# untitled.net
KiCad netlist of a schematic drawn in EAGLE
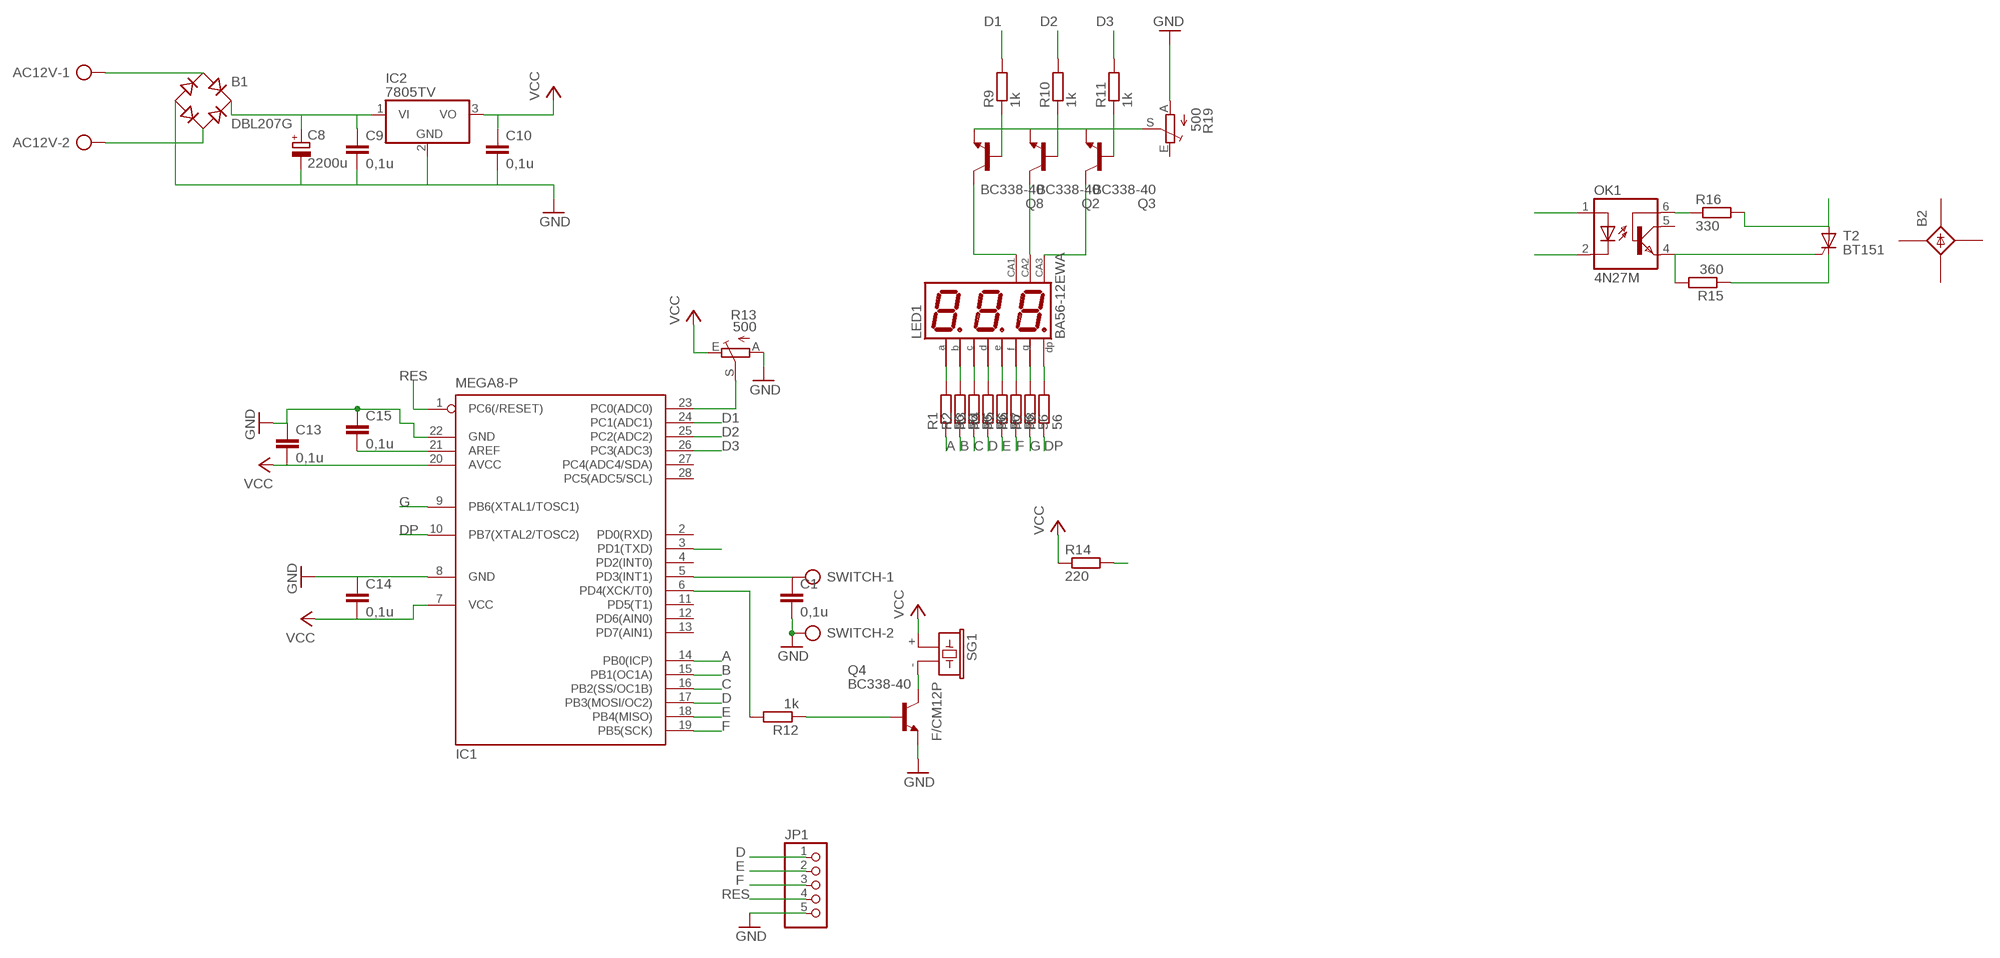
[diagram p0: schematic, sheet 1]

(export (version "E")
  (design (tool "Eeschema 10.0.6"))
  (components
    (comp (ref "AC12V")
      (value "AK500/2")
      (footprint "eagle-import:AK500_2")
      (libsource (lib "eagle-import") (part "AK500/2"))
    )
    (comp (ref "B1")
      (value "DBL207G")
      (footprint "eagle-import:DB")
      (libsource (lib "eagle-import") (part "DB?GL207"))
    )
    (comp (ref "B2")
      (value "B25A-")
      (footprint "eagle-import:B25A-")
      (libsource (lib "eagle-import") (part "B25A-"))
    )
    (comp (ref "C1")
      (value "0,1u")
      (footprint "eagle-import:C1206K")
      (libsource (lib "eagle-import") (part "C-EUC1206K"))
    )
    (comp (ref "C8")
      (value "2200u")
      (footprint "eagle-import:E7,5-16")
      (libsource (lib "eagle-import") (part "CPOL-EUE7.5-16"))
    )
    (comp (ref "C9")
      (value "0,1u")
      (footprint "eagle-import:C1206K")
      (libsource (lib "eagle-import") (part "C-EUC1206K"))
    )
    (comp (ref "C10")
      (value "0,1u")
      (footprint "eagle-import:C1206K")
      (libsource (lib "eagle-import") (part "C-EUC1206K"))
    )
    (comp (ref "C13")
      (value "0,1u")
      (footprint "eagle-import:C1206K")
      (libsource (lib "eagle-import") (part "C-EUC1206K"))
    )
    (comp (ref "C14")
      (value "0,1u")
      (footprint "eagle-import:C1206K")
      (libsource (lib "eagle-import") (part "C-EUC1206K"))
    )
    (comp (ref "C15")
      (value "0,1u")
      (footprint "eagle-import:C1206K")
      (libsource (lib "eagle-import") (part "C-EUC1206K"))
    )
    (comp (ref "IC1")
      (value "MEGA8-P")
      (footprint "eagle-import:DIL28-3")
      (libsource (lib "eagle-import") (part "MEGA8-P"))
    )
    (comp (ref "IC2")
      (value "7805TV")
      (footprint "eagle-import:TO220V")
      (libsource (lib "eagle-import") (part "78TV05"))
    )
    (comp (ref "JP1")
      (value "PINHD-1X5")
      (footprint "eagle-import:1X05")
      (libsource (lib "eagle-import") (part "PINHD-1X5"))
    )
    (comp (ref "LED1")
      (value "BA56-12EWA")
      (footprint "eagle-import:BX56-12")
      (libsource (lib "eagle-import") (part "B?56-12WAAE"))
    )
    (comp (ref "OK1")
      (value "4N27M")
      (footprint "eagle-import:DIL06")
      (fields (field (name "MF") "FAIRCHILD SEMICONDUCTOR"))
      (libsource (lib "eagle-import") (part "4N?M27"))
    )
    (comp (ref "Q2")
      (value "BC338-40")
      (footprint "eagle-import:TO92-EBC")
      (libsource (lib "eagle-import") (part "BC338-40"))
    )
    (comp (ref "Q3")
      (value "BC338-40")
      (footprint "eagle-import:TO92-EBC")
      (libsource (lib "eagle-import") (part "BC338-40"))
    )
    (comp (ref "Q4")
      (value "BC338-40")
      (footprint "eagle-import:TO92-EBC")
      (libsource (lib "eagle-import") (part "BC338-40"))
    )
    (comp (ref "Q8")
      (value "BC338-40")
      (footprint "eagle-import:TO92-EBC")
      (libsource (lib "eagle-import") (part "BC338-40"))
    )
    (comp (ref "R1")
      (value "56")
      (footprint "eagle-import:0204_7")
      (libsource (lib "eagle-import") (part "R-EU_0204/7"))
    )
    (comp (ref "R2")
      (value "56")
      (footprint "eagle-import:0204_7")
      (libsource (lib "eagle-import") (part "R-EU_0204/7"))
    )
    (comp (ref "R3")
      (value "56")
      (footprint "eagle-import:0204_7")
      (libsource (lib "eagle-import") (part "R-EU_0204/7"))
    )
    (comp (ref "R4")
      (value "56")
      (footprint "eagle-import:0204_7")
      (libsource (lib "eagle-import") (part "R-EU_0204/7"))
    )
    (comp (ref "R5")
      (value "56")
      (footprint "eagle-import:0204_7")
      (libsource (lib "eagle-import") (part "R-EU_0204/7"))
    )
    (comp (ref "R6")
      (value "56")
      (footprint "eagle-import:0204_7")
      (libsource (lib "eagle-import") (part "R-EU_0204/7"))
    )
    (comp (ref "R7")
      (value "56")
      (footprint "eagle-import:0204_7")
      (libsource (lib "eagle-import") (part "R-EU_0204/7"))
    )
    (comp (ref "R8")
      (value "56")
      (footprint "eagle-import:0204_7")
      (libsource (lib "eagle-import") (part "R-EU_0204/7"))
    )
    (comp (ref "R9")
      (value "1k")
      (footprint "eagle-import:0204_7")
      (libsource (lib "eagle-import") (part "R-EU_0204/7"))
    )
    (comp (ref "R10")
      (value "1k")
      (footprint "eagle-import:0204_7")
      (libsource (lib "eagle-import") (part "R-EU_0204/7"))
    )
    (comp (ref "R11")
      (value "1k")
      (footprint "eagle-import:0204_7")
      (libsource (lib "eagle-import") (part "R-EU_0204/7"))
    )
    (comp (ref "R12")
      (value "1k")
      (footprint "eagle-import:0204_7")
      (libsource (lib "eagle-import") (part "R-EU_0204/7"))
    )
    (comp (ref "R13")
      (value "500")
      (footprint "eagle-import:CA6V")
      (libsource (lib "eagle-import") (part "TRIM_EU-CA6V"))
    )
    (comp (ref "R14")
      (value "220")
      (footprint "eagle-import:0204_7")
      (libsource (lib "eagle-import") (part "R-EU_0204/7"))
    )
    (comp (ref "R15")
      (value "360")
      (footprint "eagle-import:0204_7")
      (libsource (lib "eagle-import") (part "R-EU_0204/7"))
    )
    (comp (ref "R16")
      (value "330")
      (footprint "eagle-import:0204_7")
      (libsource (lib "eagle-import") (part "R-EU_0204/7"))
    )
    (comp (ref "R19")
      (value "500")
      (footprint "eagle-import:CA6V")
      (libsource (lib "eagle-import") (part "TRIM_EU-CA6V"))
    )
    (comp (ref "SG1")
      (value "F/CM12P")
      (footprint "eagle-import:F_CM12P")
      (libsource (lib "eagle-import") (part "F/CM12P"))
    )
    (comp (ref "SWITCH")
      (value "AK500/2")
      (footprint "eagle-import:AK500_2")
      (libsource (lib "eagle-import") (part "AK500/2"))
    )
    (comp (ref "T2")
      (value "BT151")
      (footprint "eagle-import:TO220CL")
      (libsource (lib "eagle-import") (part "BT151"))
    )
  )
  (nets
    (net (code "1") (name "/A") (class "Default")
      (node (ref "IC1") (pin "14") (pinfunction "PB0(ICP)_14") (pintype "bidirectional"))
      (node (ref "R1") (pin "1") (pinfunction "1_1") (pintype "passive"))
    )
    (net (code "2") (name "/B") (class "Default")
      (node (ref "IC1") (pin "15") (pinfunction "PB1(OC1A)_15") (pintype "bidirectional"))
      (node (ref "R2") (pin "1") (pinfunction "1_1") (pintype "passive"))
    )
    (net (code "3") (name "/C") (class "Default")
      (node (ref "IC1") (pin "16") (pinfunction "PB2(SS/OC1B)_16") (pintype "bidirectional"))
      (node (ref "R3") (pin "1") (pinfunction "1_1") (pintype "passive"))
    )
    (net (code "4") (name "/C1") (class "Default")
      (node (ref "OK1") (pin "1") (pinfunction "A_1") (pintype "passive"))
      (node (ref "R14") (pin "2") (pinfunction "2_2") (pintype "passive"))
    )
    (net (code "5") (name "/C2") (class "Default")
      (node (ref "IC1") (pin "3") (pinfunction "PD1(TXD)_3") (pintype "bidirectional"))
      (node (ref "OK1") (pin "2") (pinfunction "C_2") (pintype "passive"))
    )
    (net (code "6") (name "/D") (class "Default")
      (node (ref "IC1") (pin "17") (pinfunction "PB3(MOSI/OC2)_17") (pintype "bidirectional"))
      (node (ref "JP1") (pin "1") (pinfunction "1_1") (pintype "passive"))
      (node (ref "R4") (pin "1") (pinfunction "1_1") (pintype "passive"))
    )
    (net (code "7") (name "/D1") (class "Default")
      (node (ref "IC1") (pin "24") (pinfunction "PC1(ADC1)_24") (pintype "bidirectional"))
      (node (ref "R9") (pin "2") (pinfunction "2_2") (pintype "passive"))
    )
    (net (code "8") (name "/D2") (class "Default")
      (node (ref "IC1") (pin "25") (pinfunction "PC2(ADC2)_25") (pintype "bidirectional"))
      (node (ref "R10") (pin "2") (pinfunction "2_2") (pintype "passive"))
    )
    (net (code "9") (name "/D3") (class "Default")
      (node (ref "IC1") (pin "26") (pinfunction "PC3(ADC3)_26") (pintype "bidirectional"))
      (node (ref "R11") (pin "2") (pinfunction "2_2") (pintype "passive"))
    )
    (net (code "10") (name "/DP") (class "Default")
      (node (ref "IC1") (pin "10") (pinfunction "PB7(XTAL2/TOSC2)_10") (pintype "bidirectional"))
      (node (ref "R8") (pin "1") (pinfunction "1_1") (pintype "passive"))
    )
    (net (code "11") (name "/E") (class "Default")
      (node (ref "IC1") (pin "18") (pinfunction "PB4(MISO)_18") (pintype "bidirectional"))
      (node (ref "JP1") (pin "2") (pinfunction "2_2") (pintype "passive"))
      (node (ref "R5") (pin "1") (pinfunction "1_1") (pintype "passive"))
    )
    (net (code "12") (name "/F") (class "Default")
      (node (ref "IC1") (pin "19") (pinfunction "PB5(SCK)_19") (pintype "bidirectional"))
      (node (ref "JP1") (pin "3") (pinfunction "3_3") (pintype "passive"))
      (node (ref "R6") (pin "1") (pinfunction "1_1") (pintype "passive"))
    )
    (net (code "13") (name "/G") (class "Default")
      (node (ref "IC1") (pin "9") (pinfunction "PB6(XTAL1/TOSC1)_9") (pintype "bidirectional"))
      (node (ref "R7") (pin "1") (pinfunction "1_1") (pintype "passive"))
    )
    (net (code "14") (name "/RES") (class "Default")
      (node (ref "IC1") (pin "1") (pinfunction "PC6(/RESET)_1") (pintype "bidirectional"))
      (node (ref "JP1") (pin "4") (pinfunction "4_4") (pintype "passive"))
    )
    (net (code "15") (name "GND") (class "Default")
      (node (ref "B1") (pin "-") (pinfunction "-_-") (pintype "passive"))
      (node (ref "C1") (pin "2") (pinfunction "2_2") (pintype "passive"))
      (node (ref "C10") (pin "2") (pinfunction "2_2") (pintype "passive"))
      (node (ref "C13") (pin "1") (pinfunction "1_1") (pintype "passive"))
      (node (ref "C14") (pin "1") (pinfunction "1_1") (pintype "passive"))
      (node (ref "C15") (pin "1") (pinfunction "1_1") (pintype "passive"))
      (node (ref "C8") (pin "-") (pinfunction "-_-") (pintype "passive"))
      (node (ref "C9") (pin "2") (pinfunction "2_2") (pintype "passive"))
      (node (ref "IC1") (pin "22") (pinfunction "GND_22") (pintype "power_in"))
      (node (ref "IC1") (pin "8") (pinfunction "GND_8") (pintype "power_in"))
      (node (ref "IC2") (pin "2") (pinfunction "GND_2") (pintype "passive"))
      (node (ref "JP1") (pin "5") (pinfunction "5_5") (pintype "passive"))
      (node (ref "Q4") (pin "E") (pinfunction "E_E") (pintype "passive"))
      (node (ref "R13") (pin "A") (pinfunction "A_A") (pintype "passive"))
      (node (ref "R19") (pin "A") (pinfunction "A_A") (pintype "passive"))
      (node (ref "SWITCH") (pin "2") (pinfunction "KL_2") (pintype "passive"))
    )
    (net (code "16") (name "Net-(AC12VA-KL)") (class "Default")
      (node (ref "AC12V") (pin "1") (pinfunction "KL_1") (pintype "passive"))
      (node (ref "B1") (pin "AC1") (pinfunction "AC1_AC1") (pintype "passive"))
    )
    (net (code "17") (name "Net-(AC12VB-KL)") (class "Default")
      (node (ref "AC12V") (pin "2") (pinfunction "KL_2") (pintype "passive"))
      (node (ref "B1") (pin "AC2") (pinfunction "AC2_AC2") (pintype "passive"))
    )
    (net (code "18") (name "Net-(IC1-AREF)") (class "Default")
      (node (ref "C15") (pin "2") (pinfunction "2_2") (pintype "passive"))
      (node (ref "IC1") (pin "21") (pinfunction "AREF_21") (pintype "passive"))
    )
    (net (code "19") (name "Net-(IC1-PC0(ADC0))") (class "Default")
      (node (ref "IC1") (pin "23") (pinfunction "PC0(ADC0)_23") (pintype "bidirectional"))
      (node (ref "R13") (pin "S") (pinfunction "S_S") (pintype "passive"))
    )
    (net (code "20") (name "Net-(IC1-PD3(INT1))") (class "Default")
      (node (ref "C1") (pin "1") (pinfunction "1_1") (pintype "passive"))
      (node (ref "IC1") (pin "5") (pinfunction "PD3(INT1)_5") (pintype "bidirectional"))
      (node (ref "SWITCH") (pin "1") (pinfunction "KL_1") (pintype "passive"))
    )
    (net (code "21") (name "Net-(IC1-PD4(XCK{slash}T0))") (class "Default")
      (node (ref "IC1") (pin "6") (pinfunction "PD4(XCK/T0)_6") (pintype "bidirectional"))
      (node (ref "R12") (pin "2") (pinfunction "2_2") (pintype "passive"))
    )
    (net (code "22") (name "Net-(IC2-VI)") (class "Default")
      (node (ref "B1") (pin "+") (pinfunction "+_+") (pintype "passive"))
      (node (ref "C8") (pin "+") (pinfunction "+_+") (pintype "passive"))
      (node (ref "C9") (pin "1") (pinfunction "1_1") (pintype "passive"))
      (node (ref "IC2") (pin "1") (pinfunction "VI_1") (pintype "input"))
    )
    (net (code "23") (name "Net-(LED1-A)") (class "Default")
      (node (ref "LED1") (pin "11") (pinfunction "A_11") (pintype "passive"))
      (node (ref "R1") (pin "2") (pinfunction "2_2") (pintype "passive"))
    )
    (net (code "24") (name "Net-(LED1-B)") (class "Default")
      (node (ref "LED1") (pin "7") (pinfunction "B_7") (pintype "passive"))
      (node (ref "R2") (pin "2") (pinfunction "2_2") (pintype "passive"))
    )
    (net (code "25") (name "Net-(LED1-C)") (class "Default")
      (node (ref "LED1") (pin "4") (pinfunction "C_4") (pintype "passive"))
      (node (ref "R3") (pin "2") (pinfunction "2_2") (pintype "passive"))
    )
    (net (code "26") (name "Net-(LED1-CA-Pad8)") (class "Default")
      (node (ref "LED1") (pin "8") (pinfunction "CA_8") (pintype "passive"))
      (node (ref "Q3") (pin "C") (pinfunction "C_C") (pintype "passive"))
    )
    (net (code "27") (name "Net-(LED1-CA-Pad9)") (class "Default")
      (node (ref "LED1") (pin "9") (pinfunction "CA_9") (pintype "passive"))
      (node (ref "Q2") (pin "C") (pinfunction "C_C") (pintype "passive"))
    )
    (net (code "28") (name "Net-(LED1-CA-Pad12)") (class "Default")
      (node (ref "LED1") (pin "12") (pinfunction "CA_12") (pintype "passive"))
      (node (ref "Q8") (pin "C") (pinfunction "C_C") (pintype "passive"))
    )
    (net (code "29") (name "Net-(LED1-D)") (class "Default")
      (node (ref "LED1") (pin "2") (pinfunction "D_2") (pintype "passive"))
      (node (ref "R4") (pin "2") (pinfunction "2_2") (pintype "passive"))
    )
    (net (code "30") (name "Net-(LED1-DP)") (class "Default")
      (node (ref "LED1") (pin "3") (pinfunction "DP_3") (pintype "passive"))
      (node (ref "R8") (pin "2") (pinfunction "2_2") (pintype "passive"))
    )
    (net (code "31") (name "Net-(LED1-E)") (class "Default")
      (node (ref "LED1") (pin "1") (pinfunction "E_1") (pintype "passive"))
      (node (ref "R5") (pin "2") (pinfunction "2_2") (pintype "passive"))
    )
    (net (code "32") (name "Net-(LED1-F)") (class "Default")
      (node (ref "LED1") (pin "10") (pinfunction "F_10") (pintype "passive"))
      (node (ref "R6") (pin "2") (pinfunction "2_2") (pintype "passive"))
    )
    (net (code "33") (name "Net-(LED1-G)") (class "Default")
      (node (ref "LED1") (pin "5") (pinfunction "G_5") (pintype "passive"))
      (node (ref "R7") (pin "2") (pinfunction "2_2") (pintype "passive"))
    )
    (net (code "34") (name "Net-(OK1-BAS)") (class "Default")
      (node (ref "OK1") (pin "6") (pinfunction "BAS_6") (pintype "passive"))
      (node (ref "R16") (pin "1") (pinfunction "1_1") (pintype "passive"))
    )
    (net (code "35") (name "Net-(OK1-EMI)") (class "Default")
      (node (ref "OK1") (pin "4") (pinfunction "EMI_4") (pintype "passive"))
      (node (ref "R15") (pin "2") (pinfunction "2_2") (pintype "passive"))
      (node (ref "T2") (pin "G") (pinfunction "G_G") (pintype "passive"))
    )
    (net (code "36") (name "Net-(Q2-PadB)") (class "Default")
      (node (ref "Q2") (pin "B") (pinfunction "B_B") (pintype "passive"))
      (node (ref "R10") (pin "1") (pinfunction "1_1") (pintype "passive"))
    )
    (net (code "37") (name "Net-(Q2-PadE)") (class "Default")
      (node (ref "Q2") (pin "E") (pinfunction "E_E") (pintype "passive"))
      (node (ref "Q3") (pin "E") (pinfunction "E_E") (pintype "passive"))
      (node (ref "Q8") (pin "E") (pinfunction "E_E") (pintype "passive"))
      (node (ref "R19") (pin "S") (pinfunction "S_S") (pintype "passive"))
    )
    (net (code "38") (name "Net-(Q3-PadB)") (class "Default")
      (node (ref "Q3") (pin "B") (pinfunction "B_B") (pintype "passive"))
      (node (ref "R11") (pin "1") (pinfunction "1_1") (pintype "passive"))
    )
    (net (code "39") (name "Net-(Q4-PadB)") (class "Default")
      (node (ref "Q4") (pin "B") (pinfunction "B_B") (pintype "passive"))
      (node (ref "R12") (pin "1") (pinfunction "1_1") (pintype "passive"))
    )
    (net (code "40") (name "Net-(Q8-PadB)") (class "Default")
      (node (ref "Q8") (pin "B") (pinfunction "B_B") (pintype "passive"))
      (node (ref "R9") (pin "1") (pinfunction "1_1") (pintype "passive"))
    )
    (net (code "41") (name "Net-(R15-Pad1)") (class "Default")
      (node (ref "R15") (pin "1") (pinfunction "1_1") (pintype "passive"))
      (node (ref "T2") (pin "C") (pinfunction "C_C") (pintype "passive"))
    )
    (net (code "42") (name "Net-(R16-Pad2)") (class "Default")
      (node (ref "R16") (pin "2") (pinfunction "2_2") (pintype "passive"))
      (node (ref "T2") (pin "A") (pinfunction "A_A") (pintype "passive"))
    )
    (net (code "43") (name "Net-(SG1-2)") (class "Default")
      (node (ref "Q4") (pin "C") (pinfunction "C_C") (pintype "passive"))
      (node (ref "SG1") (pin "-") (pinfunction "2_-") (pintype "passive"))
    )
    (net (code "44") (name "VCC") (class "Default")
      (node (ref "C10") (pin "1") (pinfunction "1_1") (pintype "passive"))
      (node (ref "C13") (pin "2") (pinfunction "2_2") (pintype "passive"))
      (node (ref "C14") (pin "2") (pinfunction "2_2") (pintype "passive"))
      (node (ref "IC1") (pin "20") (pinfunction "AVCC_20") (pintype "power_in"))
      (node (ref "IC1") (pin "7") (pinfunction "VCC_7") (pintype "power_in"))
      (node (ref "IC2") (pin "3") (pinfunction "VO_3") (pintype "passive"))
      (node (ref "R13") (pin "E") (pinfunction "E_E") (pintype "passive"))
      (node (ref "R14") (pin "1") (pinfunction "1_1") (pintype "passive"))
      (node (ref "SG1") (pin "+") (pinfunction "1_+") (pintype "passive"))
    )
    (net (code "45") (name "unconnected-(B2-+-Pad+1)") (class "Default")
      (node (ref "B2") (pin "+1") (pinfunction "+_+1") (pintype "passive"))
    )
    (net (code "46") (name "unconnected-(B2---Pad-1)") (class "Default")
      (node (ref "B2") (pin "-1") (pinfunction "-_-1") (pintype "passive"))
    )
    (net (code "47") (name "unconnected-(B2-AC1-PadAC1-)") (class "Default")
      (node (ref "B2") (pin "AC1-") (pinfunction "AC1_AC1-") (pintype "passive"))
    )
    (net (code "48") (name "unconnected-(B2-AC2-PadAC2-)") (class "Default")
      (node (ref "B2") (pin "AC2-") (pinfunction "AC2_AC2-") (pintype "passive"))
    )
    (net (code "49") (name "unconnected-(B2-Pad+)") (class "Default")
      (node (ref "B2") (pin "+") (pinfunction "+_+") (pintype "passive"))
    )
    (net (code "50") (name "unconnected-(B2-Pad-)") (class "Default")
      (node (ref "B2") (pin "-") (pinfunction "-_-") (pintype "passive"))
    )
    (net (code "51") (name "unconnected-(B2-PadAC1)") (class "Default")
      (node (ref "B2") (pin "AC1") (pinfunction "AC1_AC1") (pintype "passive"))
    )
    (net (code "52") (name "unconnected-(B2-PadAC2)") (class "Default")
      (node (ref "B2") (pin "AC2") (pinfunction "AC2_AC2") (pintype "passive"))
    )
    (net (code "53") (name "unconnected-(IC1-PC4(ADC4{slash}SDA)-Pad27)") (class "Default")
      (node (ref "IC1") (pin "27") (pinfunction "PC4(ADC4/SDA)_27") (pintype "bidirectional"))
    )
    (net (code "54") (name "unconnected-(IC1-PC5(ADC5{slash}SCL)-Pad28)") (class "Default")
      (node (ref "IC1") (pin "28") (pinfunction "PC5(ADC5/SCL)_28") (pintype "bidirectional"))
    )
    (net (code "55") (name "unconnected-(IC1-PD0(RXD)-Pad2)") (class "Default")
      (node (ref "IC1") (pin "2") (pinfunction "PD0(RXD)_2") (pintype "bidirectional"))
    )
    (net (code "56") (name "unconnected-(IC1-PD2(INT0)-Pad4)") (class "Default")
      (node (ref "IC1") (pin "4") (pinfunction "PD2(INT0)_4") (pintype "bidirectional"))
    )
    (net (code "57") (name "unconnected-(IC1-PD5(T1)-Pad11)") (class "Default")
      (node (ref "IC1") (pin "11") (pinfunction "PD5(T1)_11") (pintype "bidirectional"))
    )
    (net (code "58") (name "unconnected-(IC1-PD6(AIN0)-Pad12)") (class "Default")
      (node (ref "IC1") (pin "12") (pinfunction "PD6(AIN0)_12") (pintype "bidirectional"))
    )
    (net (code "59") (name "unconnected-(IC1-PD7(AIN1)-Pad13)") (class "Default")
      (node (ref "IC1") (pin "13") (pinfunction "PD7(AIN1)_13") (pintype "bidirectional"))
    )
    (net (code "60") (name "unconnected-(OK1-COL-Pad5)") (class "Default")
      (node (ref "OK1") (pin "5") (pinfunction "COL_5") (pintype "passive"))
    )
    (net (code "61") (name "unconnected-(R19-PadE)") (class "Default")
      (node (ref "R19") (pin "E") (pinfunction "E_E") (pintype "passive"))
    )
  )
)
